# Sheet1.net
KiCad netlist of a schematic drawn in Altium Designer
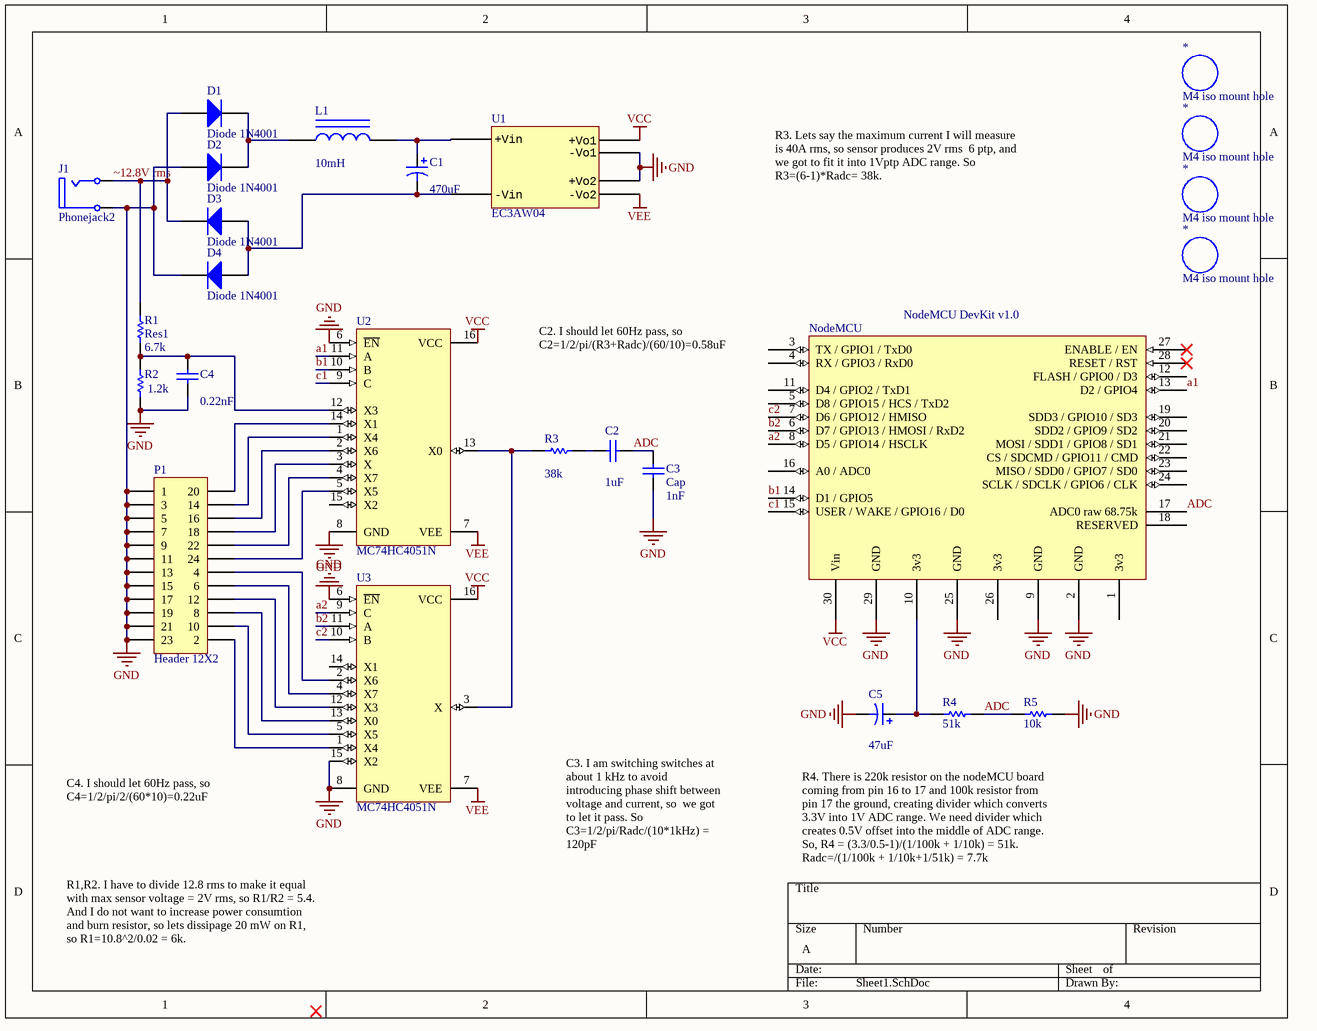
[diagram p0: Sheet1.SchDoc]

(export (version "E")
  (design (tool "Eeschema 10.0.6"))
  (components
    (comp (ref "C1")
      (value "470uF")
      (footprint "CAPPR5-12.5x25")
      (description "Polarized Capacitor (Radial)")
      (fields (field (name "Comment") "Cap Pol1") (field (name "PUBLISHER") "Altium Limited"))
      (libsource (lib "Miscellaneous Devices") (part "Cap Pol1"))
    )
    (comp (ref "C2")
      (value "1uF")
      (footprint "RAD-0.3")
      (description "Capacitor")
      (fields (field (name "Comment") "Cap") (field (name "PUBLISHER") "Altium Limited"))
      (libsource (lib "Miscellaneous Devices") (part "Cap"))
    )
    (comp (ref "C3")
      (value "Cap")
      (footprint "RAD-0.3")
      (description "Capacitor")
      (fields (field (name "ALTIUM_VALUE") "1nF") (field (name "PUBLISHER") "Altium Limited"))
      (libsource (lib "Miscellaneous Devices") (part "Cap"))
    )
    (comp (ref "C4")
      (value "0.22nF")
      (footprint "RAD-0.3")
      (description "Capacitor")
      (fields (field (name "Comment") "Cap") (field (name "PUBLISHER") "Altium Limited"))
      (libsource (lib "Miscellaneous Devices") (part "Cap"))
    )
    (comp (ref "C5")
      (value "47uF")
      (footprint "CAPPR2.5-6.3x6.8/H.9")
      (description "Polarized Capacitor (Radial)")
      (fields (field (name "Comment") "Cap Pol1") (field (name "PUBLISHER") "Altium Limited"))
      (libsource (lib "Miscellaneous Devices") (part "Cap Pol1"))
    )
    (comp (ref "D1")
      (value "Diode 1N4001")
      (footprint "DO-41")
      (description "1 Amp General Purpose Rectifier")
      (fields (field (name "PUBLISHER") "Altium Limited"))
      (libsource (lib "Miscellaneous Devices") (part "Diode 1N4001"))
    )
    (comp (ref "D2")
      (value "Diode 1N4001")
      (footprint "DO-41")
      (description "1 Amp General Purpose Rectifier")
      (fields (field (name "PUBLISHER") "Altium Limited"))
      (libsource (lib "Miscellaneous Devices") (part "Diode 1N4001"))
    )
    (comp (ref "D3")
      (value "Diode 1N4001")
      (footprint "DO-41")
      (description "1 Amp General Purpose Rectifier")
      (fields (field (name "PUBLISHER") "Altium Limited"))
      (libsource (lib "Miscellaneous Devices") (part "Diode 1N4001"))
    )
    (comp (ref "D4")
      (value "Diode 1N4001")
      (footprint "DO-41")
      (description "1 Amp General Purpose Rectifier")
      (fields (field (name "PUBLISHER") "Altium Limited"))
      (libsource (lib "Miscellaneous Devices") (part "Diode 1N4001"))
    )
    (comp (ref "J1")
      (value "Phonejack2")
      (footprint "Power jack 6x2mm")
      (description "Jack Socket, 1/4\" [6.5mm], Thru-Hole, Vertical, 2-Conductor Open Circuit")
      (fields (field (name "PUBLISHER") "Altium Limited"))
      (libsource (lib "AVP") (part "Phonejack2"))
    )
    (comp (ref "L1")
      (value "10mH")
      (footprint "Radial Vert Cylinder 10x19-6mm")
      (description "Magnetic-Core Inductor")
      (fields (field (name "Comment") "Inductor Iron") (field (name "PUBLISHER") "Altium Limited"))
      (libsource (lib "Miscellaneous Devices") (part "Inductor Iron"))
    )
    (comp (ref "NodeMCU")
      (value "NodeMCU DevKit v1.0")
      (footprint "NodeMCU DevKit v1.0 - Inside Labels")
      (libsource (lib "NodeMCU") (part "NodeMCU DevKit v1.0"))
    )
    (comp (ref "P1")
      (value "Header 12X2")
      (footprint "HDR2X12")
      (description "Header, 12-Pin, Dual row")
      (fields (field (name "PUBLISHER") "Altium Limited"))
      (libsource (lib "Miscellaneous Connectors") (part "Header 12X2"))
    )
    (comp (ref "R1")
      (value "Res1")
      (footprint "AXIAL-0.3")
      (description "Resistor")
      (fields (field (name "ALTIUM_VALUE") "6.7k") (field (name "PUBLISHER") "Altium Limited"))
      (libsource (lib "Miscellaneous Devices") (part "Res1"))
    )
    (comp (ref "R2")
      (value "1.2k")
      (footprint "AXIAL-0.3")
      (description "Resistor")
      (fields (field (name "Comment") "Res1") (field (name "PUBLISHER") "Altium Limited"))
      (libsource (lib "Miscellaneous Devices") (part "Res1"))
    )
    (comp (ref "R3")
      (value "38k")
      (footprint "AXIAL-0.3")
      (description "Resistor")
      (fields (field (name "Comment") "Res1") (field (name "PUBLISHER") "Altium Limited"))
      (libsource (lib "Miscellaneous Devices") (part "Res1"))
    )
    (comp (ref "R4")
      (value "51k")
      (footprint "AXIAL-0.3")
      (description "Resistor")
      (fields (field (name "Comment") "Res1") (field (name "PUBLISHER") "Altium Limited"))
      (libsource (lib "Miscellaneous Devices") (part "Res1"))
    )
    (comp (ref "R5")
      (value "10k")
      (footprint "AXIAL-0.3")
      (description "Resistor")
      (fields (field (name "Comment") "Res1") (field (name "PUBLISHER") "Altium Limited"))
      (libsource (lib "Miscellaneous Devices") (part "Res1"))
    )
    (comp (ref "U1") (value "EC3AW04") (footprint "EC3AW") (libsource (lib "AVP") (part "EC3AW04")))
    (comp (ref "U2")
      (value "MC74HC4051N")
      (footprint "648-08")
      (description "8-Channel Analog Multiplexer/Demultiplexer")
      (fields (field (name "PUBLISHER") "Altium Limited"))
      (libsource (lib "") (part "MC74HC4051N_1"))
    )
    (comp (ref "U3")
      (value "MC74HC4051N")
      (footprint "648-08")
      (description "8-Channel Analog Multiplexer/Demultiplexer")
      (fields (field (name "PUBLISHER") "Altium Limited"))
      (libsource (lib "ON Semi Logic Multiplexer") (part "MC74HC4051N"))
    )
  )
  (nets
    (net (code "1") (name "/ADC") (class "Default")
      (node (ref "C2") (pin "1") (pinfunction "1_1") (pintype "passive"))
      (node (ref "C3") (pin "2") (pinfunction "2_2") (pintype "passive"))
      (node (ref "NodeMCU") (pin "17") (pinfunction "ADC0_raw_68.75k_17") (pintype "passive"))
      (node (ref "R4") (pin "1") (pinfunction "1_1") (pintype "passive"))
      (node (ref "R5") (pin "2") (pinfunction "2_2") (pintype "passive"))
    )
    (net (code "2") (name "/a1") (class "Default")
      (node (ref "NodeMCU") (pin "13") (pinfunction "D2_/_GPIO4_13") (pintype "bidirectional"))
      (node (ref "U2") (pin "11") (pinfunction "A_11") (pintype "input"))
    )
    (net (code "3") (name "/a2") (class "Default")
      (node (ref "NodeMCU") (pin "8") (pinfunction "D5_/_GPIO14_/_HSCLK_8") (pintype "bidirectional"))
      (node (ref "U3") (pin "9") (pinfunction "C_9") (pintype "input"))
    )
    (net (code "4") (name "/b1") (class "Default")
      (node (ref "NodeMCU") (pin "14") (pinfunction "D1_/_GPIO5_14") (pintype "bidirectional"))
      (node (ref "U2") (pin "10") (pinfunction "B_10") (pintype "input"))
    )
    (net (code "5") (name "/b2") (class "Default")
      (node (ref "NodeMCU") (pin "6") (pinfunction "D7_/_GPIO13_/_HMOSI_/_RxD2_6") (pintype "bidirectional"))
      (node (ref "U3") (pin "11") (pinfunction "A_11") (pintype "input"))
    )
    (net (code "6") (name "/c1") (class "Default")
      (node (ref "NodeMCU") (pin "15") (pinfunction "USER_/_WAKE_/_GPIO16_/_D0_15") (pintype "bidirectional"))
      (node (ref "U2") (pin "9") (pinfunction "C_9") (pintype "input"))
    )
    (net (code "7") (name "/c2") (class "Default")
      (node (ref "NodeMCU") (pin "7") (pinfunction "D6_/_GPIO12_/_HMISO_7") (pintype "bidirectional"))
      (node (ref "U3") (pin "10") (pinfunction "B_10") (pintype "input"))
    )
    (net (code "8") (name "/~12.8V rms") (class "Default")
      (node (ref "D1") (pin "1") (pinfunction "A_1") (pintype "passive"))
      (node (ref "D3") (pin "2") (pinfunction "K_2") (pintype "passive"))
      (node (ref "J1") (pin "1") (pinfunction "T_1") (pintype "passive"))
      (node (ref "R1") (pin "2") (pinfunction "2_2") (pintype "passive"))
    )
    (net (code "9") (name "GND") (class "Default")
      (node (ref "C3") (pin "1") (pinfunction "1_1") (pintype "passive"))
      (node (ref "C4") (pin "1") (pinfunction "1_1") (pintype "passive"))
      (node (ref "C5") (pin "2") (pinfunction "2_2") (pintype "passive"))
      (node (ref "D2") (pin "1") (pinfunction "A_1") (pintype "passive"))
      (node (ref "D4") (pin "2") (pinfunction "K_2") (pintype "passive"))
      (node (ref "J1") (pin "5") (pinfunction "S_5") (pintype "power_in"))
      (node (ref "NodeMCU") (pin "2") (pinfunction "GND_2") (pintype "power_in"))
      (node (ref "NodeMCU") (pin "25") (pinfunction "GND_25") (pintype "power_in"))
      (node (ref "NodeMCU") (pin "29") (pinfunction "GND_29") (pintype "passive"))
      (node (ref "NodeMCU") (pin "9") (pinfunction "GND_9") (pintype "power_in"))
      (node (ref "P1") (pin "1") (pinfunction "1_1") (pintype "passive"))
      (node (ref "P1") (pin "11") (pinfunction "11_11") (pintype "passive"))
      (node (ref "P1") (pin "13") (pinfunction "13_13") (pintype "passive"))
      (node (ref "P1") (pin "15") (pinfunction "15_15") (pintype "passive"))
      (node (ref "P1") (pin "17") (pinfunction "17_17") (pintype "passive"))
      (node (ref "P1") (pin "19") (pinfunction "19_19") (pintype "passive"))
      (node (ref "P1") (pin "21") (pinfunction "21_21") (pintype "passive"))
      (node (ref "P1") (pin "23") (pinfunction "23_23") (pintype "passive"))
      (node (ref "P1") (pin "3") (pinfunction "3_3") (pintype "passive"))
      (node (ref "P1") (pin "5") (pinfunction "5_5") (pintype "passive"))
      (node (ref "P1") (pin "7") (pinfunction "7_7") (pintype "passive"))
      (node (ref "P1") (pin "9") (pinfunction "9_9") (pintype "passive"))
      (node (ref "R2") (pin "2") (pinfunction "2_2") (pintype "passive"))
      (node (ref "R5") (pin "1") (pinfunction "1_1") (pintype "passive"))
      (node (ref "U1") (pin "10") (pinfunction "-Vo1_10") (pintype "power_in"))
      (node (ref "U1") (pin "3") (pinfunction "+Vo2_3") (pintype "power_in"))
      (node (ref "U2") (pin "6") (pinfunction "~{EN}_6") (pintype "input"))
      (node (ref "U2") (pin "8") (pinfunction "GND_8") (pintype "power_in"))
      (node (ref "U3") (pin "15") (pinfunction "X2_15") (pintype "bidirectional"))
      (node (ref "U3") (pin "6") (pinfunction "~{EN}_6") (pintype "input"))
      (node (ref "U3") (pin "8") (pinfunction "GND_8") (pintype "power_in"))
    )
    (net (code "10") (name "Net-(C2-Pad2)") (class "Default")
      (node (ref "C2") (pin "2") (pinfunction "2_2") (pintype "passive"))
      (node (ref "R3") (pin "2") (pinfunction "2_2") (pintype "passive"))
    )
    (net (code "11") (name "Net-(C5-Pad1)") (class "Default")
      (node (ref "C5") (pin "1") (pinfunction "1_1") (pintype "passive"))
      (node (ref "NodeMCU") (pin "10") (pinfunction "3v3_10") (pintype "power_in"))
      (node (ref "R4") (pin "2") (pinfunction "2_2") (pintype "passive"))
    )
    (net (code "12") (name "Net-(D1-K)") (class "Default")
      (node (ref "D1") (pin "2") (pinfunction "K_2") (pintype "passive"))
      (node (ref "D2") (pin "2") (pinfunction "K_2") (pintype "passive"))
      (node (ref "L1") (pin "1") (pinfunction "1_1") (pintype "passive"))
    )
    (net (code "13") (name "Net-(D3-A)") (class "Default")
      (node (ref "C1") (pin "2") (pinfunction "2_2") (pintype "passive"))
      (node (ref "D3") (pin "1") (pinfunction "A_1") (pintype "passive"))
      (node (ref "D4") (pin "1") (pinfunction "A_1") (pintype "passive"))
      (node (ref "U1") (pin "12") (pinfunction "-Vin_12") (pintype "power_in"))
    )
    (net (code "14") (name "Net-(U1-+Vin)") (class "Default")
      (node (ref "C1") (pin "1") (pinfunction "1_1") (pintype "passive"))
      (node (ref "L1") (pin "2") (pinfunction "2_2") (pintype "passive"))
      (node (ref "U1") (pin "1") (pinfunction "+Vin_1") (pintype "power_in"))
    )
    (net (code "15") (name "Net-(U2-X)") (class "Default")
      (node (ref "P1") (pin "18") (pinfunction "18_18") (pintype "passive"))
      (node (ref "U2") (pin "3") (pinfunction "X_3") (pintype "bidirectional"))
    )
    (net (code "16") (name "Net-(U2-X0)") (class "Default")
      (node (ref "R3") (pin "1") (pinfunction "1_1") (pintype "passive"))
      (node (ref "U2") (pin "13") (pinfunction "X0_13") (pintype "bidirectional"))
      (node (ref "U3") (pin "3") (pinfunction "X_3") (pintype "bidirectional"))
    )
    (net (code "17") (name "Net-(U2-X1)") (class "Default")
      (node (ref "P1") (pin "20") (pinfunction "20_20") (pintype "passive"))
      (node (ref "U2") (pin "14") (pinfunction "X1_14") (pintype "bidirectional"))
    )
    (net (code "18") (name "Net-(U2-X3)") (class "Default")
      (node (ref "C4") (pin "2") (pinfunction "2_2") (pintype "passive"))
      (node (ref "R1") (pin "1") (pinfunction "1_1") (pintype "passive"))
      (node (ref "R2") (pin "1") (pinfunction "1_1") (pintype "passive"))
      (node (ref "U2") (pin "12") (pinfunction "X3_12") (pintype "bidirectional"))
    )
    (net (code "19") (name "Net-(U2-X4)") (class "Default")
      (node (ref "P1") (pin "14") (pinfunction "14_14") (pintype "passive"))
      (node (ref "U2") (pin "1") (pinfunction "X4_1") (pintype "bidirectional"))
    )
    (net (code "20") (name "Net-(U2-X5)") (class "Default")
      (node (ref "P1") (pin "24") (pinfunction "24_24") (pintype "passive"))
      (node (ref "U2") (pin "5") (pinfunction "X5_5") (pintype "bidirectional"))
    )
    (net (code "21") (name "Net-(U2-X6)") (class "Default")
      (node (ref "P1") (pin "16") (pinfunction "16_16") (pintype "passive"))
      (node (ref "U2") (pin "2") (pinfunction "X6_2") (pintype "bidirectional"))
    )
    (net (code "22") (name "Net-(U2-X7)") (class "Default")
      (node (ref "P1") (pin "22") (pinfunction "22_22") (pintype "passive"))
      (node (ref "U2") (pin "4") (pinfunction "X7_4") (pintype "bidirectional"))
    )
    (net (code "23") (name "Net-(U3-X0)") (class "Default")
      (node (ref "P1") (pin "8") (pinfunction "8_8") (pintype "passive"))
      (node (ref "U3") (pin "13") (pinfunction "X0_13") (pintype "bidirectional"))
    )
    (net (code "24") (name "Net-(U3-X3)") (class "Default")
      (node (ref "P1") (pin "12") (pinfunction "12_12") (pintype "passive"))
      (node (ref "U3") (pin "12") (pinfunction "X3_12") (pintype "bidirectional"))
    )
    (net (code "25") (name "Net-(U3-X4)") (class "Default")
      (node (ref "P1") (pin "2") (pinfunction "2_2") (pintype "passive"))
      (node (ref "U3") (pin "1") (pinfunction "X4_1") (pintype "bidirectional"))
    )
    (net (code "26") (name "Net-(U3-X5)") (class "Default")
      (node (ref "P1") (pin "10") (pinfunction "10_10") (pintype "passive"))
      (node (ref "U3") (pin "5") (pinfunction "X5_5") (pintype "bidirectional"))
    )
    (net (code "27") (name "Net-(U3-X6)") (class "Default")
      (node (ref "P1") (pin "4") (pinfunction "4_4") (pintype "passive"))
      (node (ref "U3") (pin "2") (pinfunction "X6_2") (pintype "bidirectional"))
    )
    (net (code "28") (name "Net-(U3-X7)") (class "Default")
      (node (ref "P1") (pin "6") (pinfunction "6_6") (pintype "passive"))
      (node (ref "U3") (pin "4") (pinfunction "X7_4") (pintype "bidirectional"))
    )
    (net (code "29") (name "VCC") (class "Default")
      (node (ref "NodeMCU") (pin "30") (pinfunction "Vin_30") (pintype "passive"))
      (node (ref "U1") (pin "11") (pinfunction "+Vo1_11") (pintype "power_in"))
      (node (ref "U2") (pin "16") (pinfunction "VCC_16") (pintype "power_in"))
      (node (ref "U3") (pin "16") (pinfunction "VCC_16") (pintype "power_in"))
    )
    (net (code "30") (name "VEE") (class "Default")
      (node (ref "U1") (pin "2") (pinfunction "-Vo2_2") (pintype "power_in"))
      (node (ref "U2") (pin "7") (pinfunction "VEE_7") (pintype "power_in"))
      (node (ref "U3") (pin "7") (pinfunction "VEE_7") (pintype "power_in"))
    )
    (net (code "31") (name "unconnected-(NodeMCU-3v3-Pad1)") (class "Default")
      (node (ref "NodeMCU") (pin "1") (pinfunction "3v3_1") (pintype "power_in"))
    )
    (net (code "32") (name "unconnected-(NodeMCU-3v3-Pad26)") (class "Default")
      (node (ref "NodeMCU") (pin "26") (pinfunction "3v3_26") (pintype "power_in"))
    )
    (net (code "33") (name "unconnected-(NodeMCU-A0_{slash}_ADC0-Pad16)") (class "Default")
      (node (ref "NodeMCU") (pin "16") (pinfunction "A0_/_ADC0_16") (pintype "bidirectional"))
    )
    (net (code "34") (name "unconnected-(NodeMCU-CS_{slash}_SDCMD_{slash}_GPIO11_{slash}_CMD-Pad22)") (class "Default")
      (node (ref "NodeMCU") (pin "22") (pinfunction "CS_/_SDCMD_/_GPIO11_/_CMD_22") (pintype "bidirectional"))
    )
    (net (code "35") (name "unconnected-(NodeMCU-D4_{slash}_GPIO2_{slash}_TxD1-Pad11)") (class "Default")
      (node (ref "NodeMCU") (pin "11") (pinfunction "D4_/_GPIO2_/_TxD1_11") (pintype "bidirectional"))
    )
    (net (code "36") (name "unconnected-(NodeMCU-D8_{slash}_GPIO15_{slash}_HCS_{slash}_TxD2-Pad5)") (class "Default")
      (node (ref "NodeMCU") (pin "5") (pinfunction "D8_/_GPIO15_/_HCS_/_TxD2_5") (pintype "bidirectional"))
    )
    (net (code "37") (name "unconnected-(NodeMCU-ENABLE_{slash}_EN-Pad27)") (class "Default")
      (node (ref "NodeMCU") (pin "27") (pinfunction "ENABLE_/_EN_27") (pintype "input+no_connect"))
    )
    (net (code "38") (name "unconnected-(NodeMCU-FLASH_{slash}_GPIO0_{slash}_D3-Pad12)") (class "Default")
      (node (ref "NodeMCU") (pin "12") (pinfunction "FLASH_/_GPIO0_/_D3_12") (pintype "bidirectional"))
    )
    (net (code "39") (name "unconnected-(NodeMCU-MISO_{slash}_SDD0_{slash}_GPIO7_{slash}_SD0-Pad23)") (class "Default")
      (node (ref "NodeMCU") (pin "23") (pinfunction "MISO_/_SDD0_/_GPIO7_/_SD0_23") (pintype "bidirectional"))
    )
    (net (code "40") (name "unconnected-(NodeMCU-MOSI_{slash}_SDD1_{slash}_GPIO8_{slash}_SD1-Pad21)") (class "Default")
      (node (ref "NodeMCU") (pin "21") (pinfunction "MOSI_/_SDD1_/_GPIO8_/_SD1_21") (pintype "bidirectional"))
    )
    (net (code "41") (name "unconnected-(NodeMCU-RESERVED-Pad18)") (class "Default")
      (node (ref "NodeMCU") (pin "18") (pinfunction "RESERVED_18") (pintype "passive"))
    )
    (net (code "42") (name "unconnected-(NodeMCU-RESET_{slash}_RST-Pad28)") (class "Default")
      (node (ref "NodeMCU") (pin "28") (pinfunction "RESET_/_RST_28") (pintype "input+no_connect"))
    )
    (net (code "43") (name "unconnected-(NodeMCU-RX_{slash}_GPIO3_{slash}_RxD0-Pad4)") (class "Default")
      (node (ref "NodeMCU") (pin "4") (pinfunction "RX_/_GPIO3_/_RxD0_4") (pintype "bidirectional"))
    )
    (net (code "44") (name "unconnected-(NodeMCU-SCLK_{slash}_SDCLK_{slash}_GPIO6_{slash}_CLK-Pad24)") (class "Default")
      (node (ref "NodeMCU") (pin "24") (pinfunction "SCLK_/_SDCLK_/_GPIO6_/_CLK_24") (pintype "bidirectional"))
    )
    (net (code "45") (name "unconnected-(NodeMCU-SDD2_{slash}_GPIO9_{slash}_SD2-Pad20)") (class "Default")
      (node (ref "NodeMCU") (pin "20") (pinfunction "SDD2_/_GPIO9_/_SD2_20") (pintype "bidirectional"))
    )
    (net (code "46") (name "unconnected-(NodeMCU-SDD3_{slash}_GPIO10_{slash}_SD3-Pad19)") (class "Default")
      (node (ref "NodeMCU") (pin "19") (pinfunction "SDD3_/_GPIO10_/_SD3_19") (pintype "bidirectional"))
    )
    (net (code "47") (name "unconnected-(NodeMCU-TX_{slash}_GPIO1_{slash}_TxD0-Pad3)") (class "Default")
      (node (ref "NodeMCU") (pin "3") (pinfunction "TX_/_GPIO1_/_TxD0_3") (pintype "bidirectional"))
    )
    (net (code "48") (name "unconnected-(U2-X2-Pad15)") (class "Default")
      (node (ref "U2") (pin "15") (pinfunction "X2_15") (pintype "bidirectional"))
    )
    (net (code "49") (name "unconnected-(U3-X1-Pad14)") (class "Default")
      (node (ref "U3") (pin "14") (pinfunction "X1_14") (pintype "bidirectional"))
    )
  )
)
